# ocape.net
KiCad netlist of a schematic drawn in EAGLE
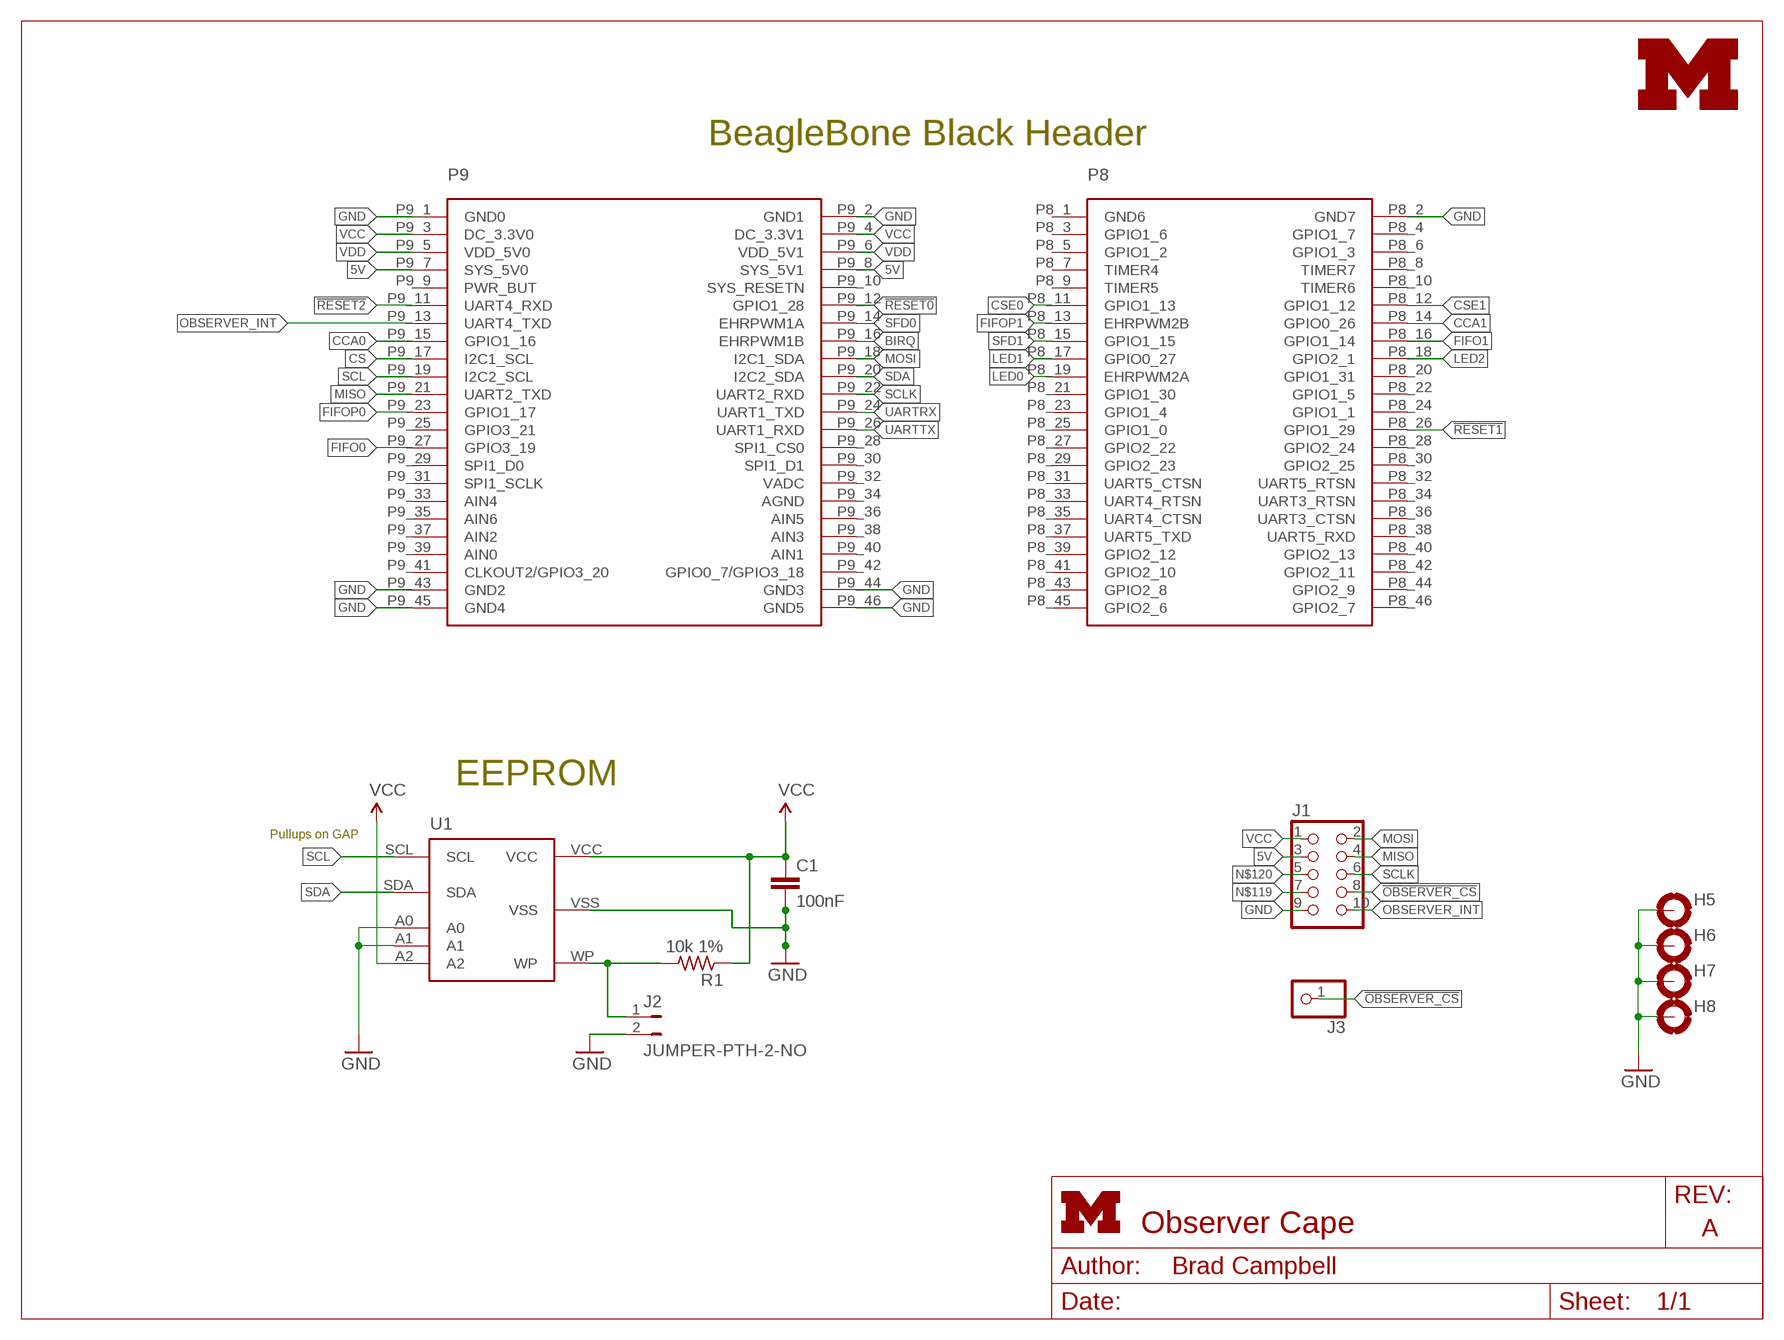
[diagram p0: schematic, sheet 1]

(export (version "E")
  (design (tool "Eeschema 10.0.6"))
  (components
    (comp (ref "C1")
      (value "100nF")
      (footprint "eagle-import:C0402")
      (libsource (lib "eagle-import") (part "C-EUC0402"))
    )
    (comp (ref "H5")
      (value "MOUNT-PAD-ROUND3.2")
      (footprint "eagle-import:3,2-PAD")
      (libsource (lib "eagle-import") (part "MOUNT-PAD-ROUND3.2"))
    )
    (comp (ref "H6")
      (value "MOUNT-PAD-ROUND3.2")
      (footprint "eagle-import:3,2-PAD")
      (libsource (lib "eagle-import") (part "MOUNT-PAD-ROUND3.2"))
    )
    (comp (ref "H7")
      (value "MOUNT-PAD-ROUND3.2")
      (footprint "eagle-import:3,2-PAD")
      (libsource (lib "eagle-import") (part "MOUNT-PAD-ROUND3.2"))
    )
    (comp (ref "H8")
      (value "MOUNT-PAD-ROUND3.2")
      (footprint "eagle-import:3,2-PAD")
      (libsource (lib "eagle-import") (part "MOUNT-PAD-ROUND3.2"))
    )
    (comp (ref "J1")
      (value "CON_HEADER_2X05-PTH+SHROUDED_A")
      (footprint "eagle-import:PINSHRD_PTH_2X05")
      (libsource (lib "eagle-import") (part "CON_HEADER_2X05-PTH+SHROUDED_A"))
    )
    (comp (ref "J2")
      (value "JUMPER-PTH-2-NO")
      (footprint "eagle-import:PTH-JUMPER-2-NO_NO_SILK")
      (libsource (lib "eagle-import") (part "JUMPER-PTH-2-NO"))
    )
    (comp (ref "J3")
      (value "PINHD-1X1")
      (footprint "eagle-import:1X01")
      (libsource (lib "eagle-import") (part "PINHD-1X1"))
    )
    (comp (ref "LOGO1")
      (value "UMICH_SOLID_SMALL")
      (footprint "eagle-import:UMICH_SOLID_75MIL")
      (libsource (lib "eagle-import") (part "UMICH_SOLID_SMALL"))
    )
    (comp (ref "P9/P8")
      (value "BBB_HEADERS")
      (footprint "eagle-import:BBB_HEADERS")
      (libsource (lib "eagle-import") (part "BBB_HEADERS"))
    )
    (comp (ref "R1")
      (value "10k 1%")
      (footprint "eagle-import:R0402")
      (libsource (lib "eagle-import") (part "R-US_R0402"))
    )
    (comp (ref "U1")
      (value "CAT24C256WI-GT3")
      (footprint "eagle-import:CAT24C256WI-GT3")
      (libsource (lib "eagle-import") (part "CAT24C256WI-GT3"))
    )
  )
  (nets
    (net (code "1") (name "/~{OBSERVER_CS}") (class "Default")
      (node (ref "J1") (pin "8") (pinfunction "8_8") (pintype "passive"))
      (node (ref "J3") (pin "1") (pinfunction "1_1") (pintype "passive"))
    )
    (net (code "2") (name "/~{RESET0}") (class "Default")
      (node (ref "P9/P8") (pin "P9_12") (pinfunction "GPIO1_28_P9_12") (pintype "bidirectional"))
    )
    (net (code "3") (name "/~{RESET1}") (class "Default")
      (node (ref "P9/P8") (pin "P8_26") (pinfunction "GPIO1_29_P8_26") (pintype "bidirectional"))
    )
    (net (code "4") (name "/~{RESET2}") (class "Default")
      (node (ref "P9/P8") (pin "P9_11") (pinfunction "UART4_RXD_P9_11") (pintype "bidirectional"))
    )
    (net (code "5") (name "5V") (class "Default")
      (node (ref "J1") (pin "3") (pinfunction "3_3") (pintype "passive"))
      (node (ref "P9/P8") (pin "P9_7") (pinfunction "SYS_5V0_P9_7") (pintype "bidirectional"))
      (node (ref "P9/P8") (pin "P9_8") (pinfunction "SYS_5V1_P9_8") (pintype "bidirectional"))
    )
    (net (code "6") (name "BIRQ") (class "Default")
      (node (ref "P9/P8") (pin "P9_16") (pinfunction "EHRPWM1B_P9_16") (pintype "bidirectional"))
    )
    (net (code "7") (name "CCA0") (class "Default")
      (node (ref "P9/P8") (pin "P9_15") (pinfunction "GPIO1_16_P9_15") (pintype "bidirectional"))
    )
    (net (code "8") (name "CCA1") (class "Default")
      (node (ref "P9/P8") (pin "P8_14") (pinfunction "GPIO0_26_P8_14") (pintype "bidirectional"))
    )
    (net (code "9") (name "CS") (class "Default")
      (node (ref "P9/P8") (pin "P9_17") (pinfunction "I2C1_SCL_P9_17") (pintype "bidirectional"))
    )
    (net (code "10") (name "CSE0") (class "Default")
      (node (ref "P9/P8") (pin "P8_11") (pinfunction "GPIO1_13_P8_11") (pintype "bidirectional"))
    )
    (net (code "11") (name "CSE1") (class "Default")
      (node (ref "P9/P8") (pin "P8_12") (pinfunction "GPIO1_12_P8_12") (pintype "bidirectional"))
    )
    (net (code "12") (name "FIFO0") (class "Default")
      (node (ref "P9/P8") (pin "P9_27") (pinfunction "GPIO3_19_P9_27") (pintype "bidirectional"))
    )
    (net (code "13") (name "FIFO1") (class "Default")
      (node (ref "P9/P8") (pin "P8_16") (pinfunction "GPIO1_14_P8_16") (pintype "bidirectional"))
    )
    (net (code "14") (name "FIFOP0") (class "Default")
      (node (ref "P9/P8") (pin "P9_23") (pinfunction "GPIO1_17_P9_23") (pintype "bidirectional"))
    )
    (net (code "15") (name "FIFOP1") (class "Default")
      (node (ref "P9/P8") (pin "P8_13") (pinfunction "EHRPWM2B_P8_13") (pintype "bidirectional"))
    )
    (net (code "16") (name "GND") (class "Default")
      (node (ref "C1") (pin "2") (pinfunction "2_2") (pintype "passive"))
      (node (ref "H5") (pin "B3,2") (pinfunction "MOUNT_B3,2") (pintype "passive"))
      (node (ref "H6") (pin "B3,2") (pinfunction "MOUNT_B3,2") (pintype "passive"))
      (node (ref "H7") (pin "B3,2") (pinfunction "MOUNT_B3,2") (pintype "passive"))
      (node (ref "H8") (pin "B3,2") (pinfunction "MOUNT_B3,2") (pintype "passive"))
      (node (ref "J1") (pin "9") (pinfunction "9_9") (pintype "passive"))
      (node (ref "J2") (pin "2") (pinfunction "2_2") (pintype "passive"))
      (node (ref "P9/P8") (pin "P8_2") (pinfunction "GND7_P8_2") (pintype "bidirectional"))
      (node (ref "P9/P8") (pin "P9_1") (pinfunction "GND0_P9_1") (pintype "bidirectional"))
      (node (ref "P9/P8") (pin "P9_2") (pinfunction "GND1_P9_2") (pintype "bidirectional"))
      (node (ref "P9/P8") (pin "P9_43") (pinfunction "GND2_P9_43") (pintype "bidirectional"))
      (node (ref "P9/P8") (pin "P9_44") (pinfunction "GND3_P9_44") (pintype "bidirectional"))
      (node (ref "P9/P8") (pin "P9_45") (pinfunction "GND4_P9_45") (pintype "bidirectional"))
      (node (ref "P9/P8") (pin "P9_46") (pinfunction "GND5_P9_46") (pintype "bidirectional"))
      (node (ref "U1") (pin "A0") (pinfunction "A0_A0") (pintype "bidirectional"))
      (node (ref "U1") (pin "A1") (pinfunction "A1_A1") (pintype "bidirectional"))
      (node (ref "U1") (pin "VSS") (pinfunction "VSS_VSS") (pintype "bidirectional"))
    )
    (net (code "17") (name "LED0") (class "Default")
      (node (ref "P9/P8") (pin "P8_19") (pinfunction "EHRPWM2A_P8_19") (pintype "bidirectional"))
    )
    (net (code "18") (name "LED1") (class "Default")
      (node (ref "P9/P8") (pin "P8_17") (pinfunction "GPIO0_27_P8_17") (pintype "bidirectional"))
    )
    (net (code "19") (name "LED2") (class "Default")
      (node (ref "P9/P8") (pin "P8_18") (pinfunction "GPIO2_1_P8_18") (pintype "bidirectional"))
    )
    (net (code "20") (name "MISO") (class "Default")
      (node (ref "J1") (pin "4") (pinfunction "4_4") (pintype "passive"))
      (node (ref "P9/P8") (pin "P9_21") (pinfunction "UART2_TXD_P9_21") (pintype "bidirectional"))
    )
    (net (code "21") (name "MOSI") (class "Default")
      (node (ref "J1") (pin "2") (pinfunction "2_2") (pintype "passive"))
      (node (ref "P9/P8") (pin "P9_18") (pinfunction "I2C1_SDA_P9_18") (pintype "bidirectional"))
    )
    (net (code "22") (name "N$119") (class "Default")
      (node (ref "J1") (pin "7") (pinfunction "7_7") (pintype "passive"))
    )
    (net (code "23") (name "N$120") (class "Default")
      (node (ref "J1") (pin "5") (pinfunction "5_5") (pintype "passive"))
    )
    (net (code "24") (name "Net-(J2-Pad1)") (class "Default")
      (node (ref "J2") (pin "1") (pinfunction "1_1") (pintype "passive"))
      (node (ref "R1") (pin "2") (pinfunction "2_2") (pintype "passive"))
      (node (ref "U1") (pin "WP") (pinfunction "WP_WP") (pintype "bidirectional"))
    )
    (net (code "25") (name "OBSERVER_INT") (class "Default")
      (node (ref "J1") (pin "10") (pinfunction "10_10") (pintype "passive"))
      (node (ref "P9/P8") (pin "P9_13") (pinfunction "UART4_TXD_P9_13") (pintype "bidirectional"))
    )
    (net (code "26") (name "SCL") (class "Default")
      (node (ref "P9/P8") (pin "P9_19") (pinfunction "I2C2_SCL_P9_19") (pintype "bidirectional"))
      (node (ref "U1") (pin "SCL") (pinfunction "SCL_SCL") (pintype "bidirectional"))
    )
    (net (code "27") (name "SCLK") (class "Default")
      (node (ref "J1") (pin "6") (pinfunction "6_6") (pintype "passive"))
      (node (ref "P9/P8") (pin "P9_22") (pinfunction "UART2_RXD_P9_22") (pintype "bidirectional"))
    )
    (net (code "28") (name "SDA") (class "Default")
      (node (ref "P9/P8") (pin "P9_20") (pinfunction "I2C2_SDA_P9_20") (pintype "bidirectional"))
      (node (ref "U1") (pin "SDA") (pinfunction "SDA_SDA") (pintype "bidirectional"))
    )
    (net (code "29") (name "SFD0") (class "Default")
      (node (ref "P9/P8") (pin "P9_14") (pinfunction "EHRPWM1A_P9_14") (pintype "bidirectional"))
    )
    (net (code "30") (name "SFD1") (class "Default")
      (node (ref "P9/P8") (pin "P8_15") (pinfunction "GPIO1_15_P8_15") (pintype "bidirectional"))
    )
    (net (code "31") (name "UARTRX") (class "Default")
      (node (ref "P9/P8") (pin "P9_24") (pinfunction "UART1_TXD_P9_24") (pintype "bidirectional"))
    )
    (net (code "32") (name "UARTTX") (class "Default")
      (node (ref "P9/P8") (pin "P9_26") (pinfunction "UART1_RXD_P9_26") (pintype "bidirectional"))
    )
    (net (code "33") (name "VCC") (class "Default")
      (node (ref "C1") (pin "1") (pinfunction "1_1") (pintype "passive"))
      (node (ref "J1") (pin "1") (pinfunction "1_1") (pintype "passive"))
      (node (ref "P9/P8") (pin "P9_3") (pinfunction "DC_3.3V0_P9_3") (pintype "bidirectional"))
      (node (ref "P9/P8") (pin "P9_4") (pinfunction "DC_3.3V1_P9_4") (pintype "bidirectional"))
      (node (ref "R1") (pin "1") (pinfunction "1_1") (pintype "passive"))
      (node (ref "U1") (pin "A2") (pinfunction "A2_A2") (pintype "bidirectional"))
      (node (ref "U1") (pin "VCC") (pinfunction "VCC_VCC") (pintype "bidirectional"))
    )
    (net (code "34") (name "VDD") (class "Default")
      (node (ref "P9/P8") (pin "P9_5") (pinfunction "VDD_5V0_P9_5") (pintype "bidirectional"))
      (node (ref "P9/P8") (pin "P9_6") (pinfunction "VDD_5V1_P9_6") (pintype "bidirectional"))
    )
    (net (code "35") (name "unconnected-(P9/P8-AGND-PadP9_34)") (class "Default")
      (node (ref "P9/P8") (pin "P9_34") (pinfunction "AGND_P9_34") (pintype "bidirectional"))
    )
    (net (code "36") (name "unconnected-(P9/P8-AIN0-PadP9_39)") (class "Default")
      (node (ref "P9/P8") (pin "P9_39") (pinfunction "AIN0_P9_39") (pintype "bidirectional"))
    )
    (net (code "37") (name "unconnected-(P9/P8-AIN1-PadP9_40)") (class "Default")
      (node (ref "P9/P8") (pin "P9_40") (pinfunction "AIN1_P9_40") (pintype "bidirectional"))
    )
    (net (code "38") (name "unconnected-(P9/P8-AIN2-PadP9_37)") (class "Default")
      (node (ref "P9/P8") (pin "P9_37") (pinfunction "AIN2_P9_37") (pintype "bidirectional"))
    )
    (net (code "39") (name "unconnected-(P9/P8-AIN3-PadP9_38)") (class "Default")
      (node (ref "P9/P8") (pin "P9_38") (pinfunction "AIN3_P9_38") (pintype "bidirectional"))
    )
    (net (code "40") (name "unconnected-(P9/P8-AIN4-PadP9_33)") (class "Default")
      (node (ref "P9/P8") (pin "P9_33") (pinfunction "AIN4_P9_33") (pintype "bidirectional"))
    )
    (net (code "41") (name "unconnected-(P9/P8-AIN5-PadP9_36)") (class "Default")
      (node (ref "P9/P8") (pin "P9_36") (pinfunction "AIN5_P9_36") (pintype "bidirectional"))
    )
    (net (code "42") (name "unconnected-(P9/P8-AIN6-PadP9_35)") (class "Default")
      (node (ref "P9/P8") (pin "P9_35") (pinfunction "AIN6_P9_35") (pintype "bidirectional"))
    )
    (net (code "43") (name "unconnected-(P9/P8-CLKOUT2{slash}GPIO3_20-PadP9_41)") (class "Default")
      (node (ref "P9/P8") (pin "P9_41") (pinfunction "CLKOUT2/GPIO3_20_P9_41") (pintype "bidirectional"))
    )
    (net (code "44") (name "unconnected-(P9/P8-GND6-PadP8_1)") (class "Default")
      (node (ref "P9/P8") (pin "P8_1") (pinfunction "GND6_P8_1") (pintype "bidirectional"))
    )
    (net (code "45") (name "unconnected-(P9/P8-GPIO0_7{slash}GPIO3_18-PadP9_42)") (class "Default")
      (node (ref "P9/P8") (pin "P9_42") (pinfunction "GPIO0_7/GPIO3_18_P9_42") (pintype "bidirectional"))
    )
    (net (code "46") (name "unconnected-(P9/P8-GPIO1_0-PadP8_25)") (class "Default")
      (node (ref "P9/P8") (pin "P8_25") (pinfunction "GPIO1_0_P8_25") (pintype "bidirectional"))
    )
    (net (code "47") (name "unconnected-(P9/P8-GPIO1_1-PadP8_24)") (class "Default")
      (node (ref "P9/P8") (pin "P8_24") (pinfunction "GPIO1_1_P8_24") (pintype "bidirectional"))
    )
    (net (code "48") (name "unconnected-(P9/P8-GPIO1_2-PadP8_5)") (class "Default")
      (node (ref "P9/P8") (pin "P8_5") (pinfunction "GPIO1_2_P8_5") (pintype "bidirectional"))
    )
    (net (code "49") (name "unconnected-(P9/P8-GPIO1_3-PadP8_6)") (class "Default")
      (node (ref "P9/P8") (pin "P8_6") (pinfunction "GPIO1_3_P8_6") (pintype "bidirectional"))
    )
    (net (code "50") (name "unconnected-(P9/P8-GPIO1_4-PadP8_23)") (class "Default")
      (node (ref "P9/P8") (pin "P8_23") (pinfunction "GPIO1_4_P8_23") (pintype "bidirectional"))
    )
    (net (code "51") (name "unconnected-(P9/P8-GPIO1_5-PadP8_22)") (class "Default")
      (node (ref "P9/P8") (pin "P8_22") (pinfunction "GPIO1_5_P8_22") (pintype "bidirectional"))
    )
    (net (code "52") (name "unconnected-(P9/P8-GPIO1_6-PadP8_3)") (class "Default")
      (node (ref "P9/P8") (pin "P8_3") (pinfunction "GPIO1_6_P8_3") (pintype "bidirectional"))
    )
    (net (code "53") (name "unconnected-(P9/P8-GPIO1_7-PadP8_4)") (class "Default")
      (node (ref "P9/P8") (pin "P8_4") (pinfunction "GPIO1_7_P8_4") (pintype "bidirectional"))
    )
    (net (code "54") (name "unconnected-(P9/P8-GPIO1_30-PadP8_21)") (class "Default")
      (node (ref "P9/P8") (pin "P8_21") (pinfunction "GPIO1_30_P8_21") (pintype "bidirectional"))
    )
    (net (code "55") (name "unconnected-(P9/P8-GPIO1_31-PadP8_20)") (class "Default")
      (node (ref "P9/P8") (pin "P8_20") (pinfunction "GPIO1_31_P8_20") (pintype "bidirectional"))
    )
    (net (code "56") (name "unconnected-(P9/P8-GPIO2_6-PadP8_45)") (class "Default")
      (node (ref "P9/P8") (pin "P8_45") (pinfunction "GPIO2_6_P8_45") (pintype "bidirectional"))
    )
    (net (code "57") (name "unconnected-(P9/P8-GPIO2_7-PadP8_46)") (class "Default")
      (node (ref "P9/P8") (pin "P8_46") (pinfunction "GPIO2_7_P8_46") (pintype "bidirectional"))
    )
    (net (code "58") (name "unconnected-(P9/P8-GPIO2_8-PadP8_43)") (class "Default")
      (node (ref "P9/P8") (pin "P8_43") (pinfunction "GPIO2_8_P8_43") (pintype "bidirectional"))
    )
    (net (code "59") (name "unconnected-(P9/P8-GPIO2_9-PadP8_44)") (class "Default")
      (node (ref "P9/P8") (pin "P8_44") (pinfunction "GPIO2_9_P8_44") (pintype "bidirectional"))
    )
    (net (code "60") (name "unconnected-(P9/P8-GPIO2_10-PadP8_41)") (class "Default")
      (node (ref "P9/P8") (pin "P8_41") (pinfunction "GPIO2_10_P8_41") (pintype "bidirectional"))
    )
    (net (code "61") (name "unconnected-(P9/P8-GPIO2_11-PadP8_42)") (class "Default")
      (node (ref "P9/P8") (pin "P8_42") (pinfunction "GPIO2_11_P8_42") (pintype "bidirectional"))
    )
    (net (code "62") (name "unconnected-(P9/P8-GPIO2_12-PadP8_39)") (class "Default")
      (node (ref "P9/P8") (pin "P8_39") (pinfunction "GPIO2_12_P8_39") (pintype "bidirectional"))
    )
    (net (code "63") (name "unconnected-(P9/P8-GPIO2_13-PadP8_40)") (class "Default")
      (node (ref "P9/P8") (pin "P8_40") (pinfunction "GPIO2_13_P8_40") (pintype "bidirectional"))
    )
    (net (code "64") (name "unconnected-(P9/P8-GPIO2_22-PadP8_27)") (class "Default")
      (node (ref "P9/P8") (pin "P8_27") (pinfunction "GPIO2_22_P8_27") (pintype "bidirectional"))
    )
    (net (code "65") (name "unconnected-(P9/P8-GPIO2_23-PadP8_29)") (class "Default")
      (node (ref "P9/P8") (pin "P8_29") (pinfunction "GPIO2_23_P8_29") (pintype "bidirectional"))
    )
    (net (code "66") (name "unconnected-(P9/P8-GPIO2_24-PadP8_28)") (class "Default")
      (node (ref "P9/P8") (pin "P8_28") (pinfunction "GPIO2_24_P8_28") (pintype "bidirectional"))
    )
    (net (code "67") (name "unconnected-(P9/P8-GPIO2_25-PadP8_30)") (class "Default")
      (node (ref "P9/P8") (pin "P8_30") (pinfunction "GPIO2_25_P8_30") (pintype "bidirectional"))
    )
    (net (code "68") (name "unconnected-(P9/P8-GPIO3_21-PadP9_25)") (class "Default")
      (node (ref "P9/P8") (pin "P9_25") (pinfunction "GPIO3_21_P9_25") (pintype "bidirectional"))
    )
    (net (code "69") (name "unconnected-(P9/P8-PWR_BUT-PadP9_9)") (class "Default")
      (node (ref "P9/P8") (pin "P9_9") (pinfunction "PWR_BUT_P9_9") (pintype "bidirectional"))
    )
    (net (code "70") (name "unconnected-(P9/P8-SPI1_CS0-PadP9_28)") (class "Default")
      (node (ref "P9/P8") (pin "P9_28") (pinfunction "SPI1_CS0_P9_28") (pintype "bidirectional"))
    )
    (net (code "71") (name "unconnected-(P9/P8-SPI1_D0-PadP9_29)") (class "Default")
      (node (ref "P9/P8") (pin "P9_29") (pinfunction "SPI1_D0_P9_29") (pintype "bidirectional"))
    )
    (net (code "72") (name "unconnected-(P9/P8-SPI1_D1-PadP9_30)") (class "Default")
      (node (ref "P9/P8") (pin "P9_30") (pinfunction "SPI1_D1_P9_30") (pintype "bidirectional"))
    )
    (net (code "73") (name "unconnected-(P9/P8-SPI1_SCLK-PadP9_31)") (class "Default")
      (node (ref "P9/P8") (pin "P9_31") (pinfunction "SPI1_SCLK_P9_31") (pintype "bidirectional"))
    )
    (net (code "74") (name "unconnected-(P9/P8-SYS_RESETN-PadP9_10)") (class "Default")
      (node (ref "P9/P8") (pin "P9_10") (pinfunction "SYS_RESETN_P9_10") (pintype "bidirectional"))
    )
    (net (code "75") (name "unconnected-(P9/P8-TIMER4-PadP8_7)") (class "Default")
      (node (ref "P9/P8") (pin "P8_7") (pinfunction "TIMER4_P8_7") (pintype "bidirectional"))
    )
    (net (code "76") (name "unconnected-(P9/P8-TIMER5-PadP8_9)") (class "Default")
      (node (ref "P9/P8") (pin "P8_9") (pinfunction "TIMER5_P8_9") (pintype "bidirectional"))
    )
    (net (code "77") (name "unconnected-(P9/P8-TIMER6-PadP8_10)") (class "Default")
      (node (ref "P9/P8") (pin "P8_10") (pinfunction "TIMER6_P8_10") (pintype "bidirectional"))
    )
    (net (code "78") (name "unconnected-(P9/P8-TIMER7-PadP8_8)") (class "Default")
      (node (ref "P9/P8") (pin "P8_8") (pinfunction "TIMER7_P8_8") (pintype "bidirectional"))
    )
    (net (code "79") (name "unconnected-(P9/P8-UART3_CTSN-PadP8_36)") (class "Default")
      (node (ref "P9/P8") (pin "P8_36") (pinfunction "UART3_CTSN_P8_36") (pintype "bidirectional"))
    )
    (net (code "80") (name "unconnected-(P9/P8-UART3_RTSN-PadP8_34)") (class "Default")
      (node (ref "P9/P8") (pin "P8_34") (pinfunction "UART3_RTSN_P8_34") (pintype "bidirectional"))
    )
    (net (code "81") (name "unconnected-(P9/P8-UART4_CTSN-PadP8_35)") (class "Default")
      (node (ref "P9/P8") (pin "P8_35") (pinfunction "UART4_CTSN_P8_35") (pintype "bidirectional"))
    )
    (net (code "82") (name "unconnected-(P9/P8-UART4_RTSN-PadP8_33)") (class "Default")
      (node (ref "P9/P8") (pin "P8_33") (pinfunction "UART4_RTSN_P8_33") (pintype "bidirectional"))
    )
    (net (code "83") (name "unconnected-(P9/P8-UART5_CTSN-PadP8_31)") (class "Default")
      (node (ref "P9/P8") (pin "P8_31") (pinfunction "UART5_CTSN_P8_31") (pintype "bidirectional"))
    )
    (net (code "84") (name "unconnected-(P9/P8-UART5_RTSN-PadP8_32)") (class "Default")
      (node (ref "P9/P8") (pin "P8_32") (pinfunction "UART5_RTSN_P8_32") (pintype "bidirectional"))
    )
    (net (code "85") (name "unconnected-(P9/P8-UART5_RXD-PadP8_38)") (class "Default")
      (node (ref "P9/P8") (pin "P8_38") (pinfunction "UART5_RXD_P8_38") (pintype "bidirectional"))
    )
    (net (code "86") (name "unconnected-(P9/P8-UART5_TXD-PadP8_37)") (class "Default")
      (node (ref "P9/P8") (pin "P8_37") (pinfunction "UART5_TXD_P8_37") (pintype "bidirectional"))
    )
    (net (code "87") (name "unconnected-(P9/P8-VADC-PadP9_32)") (class "Default")
      (node (ref "P9/P8") (pin "P9_32") (pinfunction "VADC_P9_32") (pintype "bidirectional"))
    )
  )
)
